# HB-Dis-EP-42BW.net
KiCad netlist of a schematic drawn in EAGLE
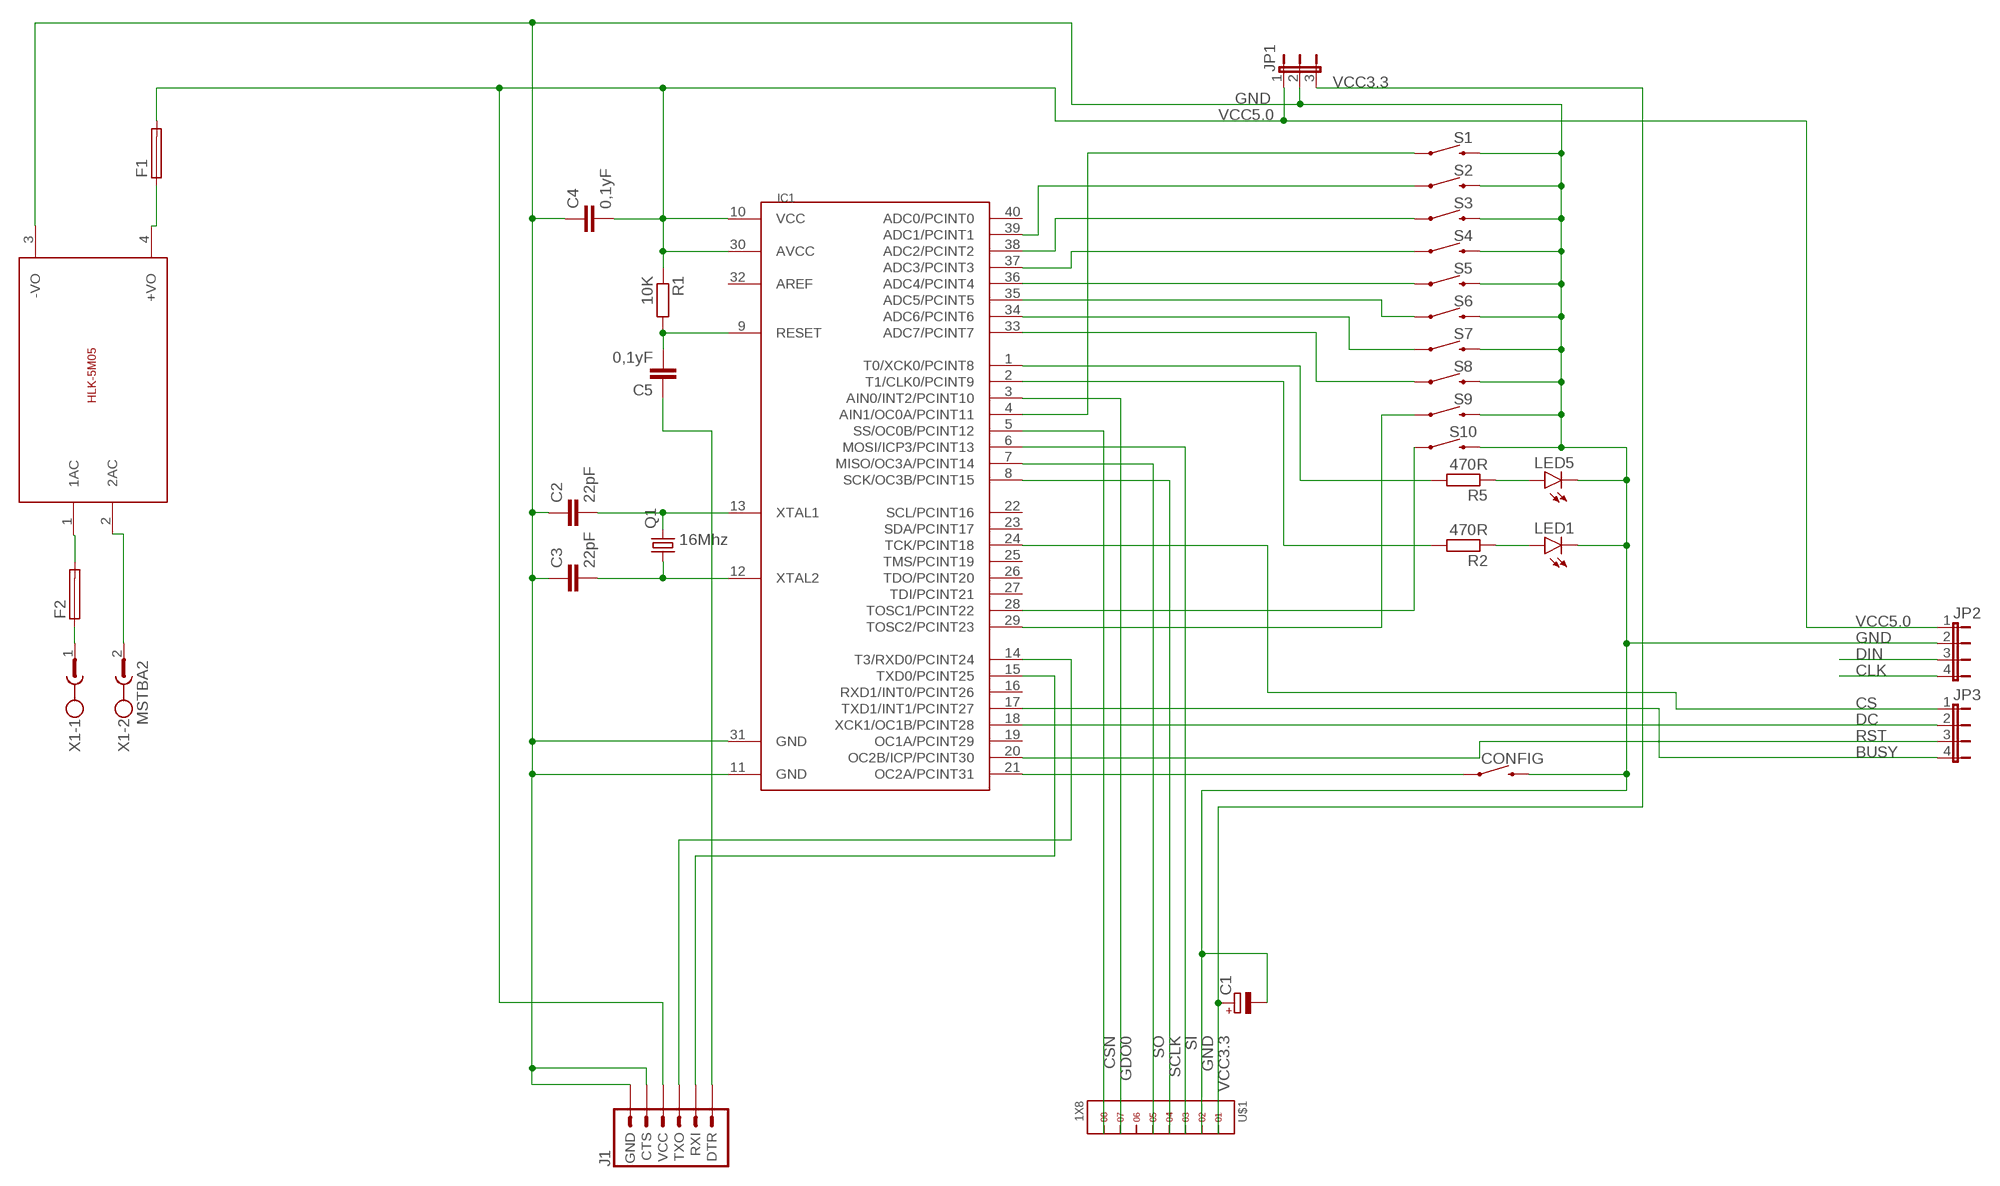
[diagram p0: schematic, sheet 1]

(export (version "E")
  (design (tool "Eeschema 10.0.6"))
  (components
    (comp (ref "C1")
      (value "CPOL-EUE2.5-5")
      (footprint "eagle-import:E2,5-5")
      (libsource (lib "eagle-import") (part "CPOL-EUE2.5-5"))
    )
    (comp (ref "C2")
      (value "22pF")
      (footprint "eagle-import:C025-024X044")
      (libsource (lib "eagle-import") (part "C-EU025-024X044"))
    )
    (comp (ref "C3")
      (value "22pF")
      (footprint "eagle-import:C025-024X044")
      (libsource (lib "eagle-import") (part "C-EU025-024X044"))
    )
    (comp (ref "C4")
      (value "0,1yF")
      (footprint "eagle-import:C025-024X044")
      (libsource (lib "eagle-import") (part "C-EU025-024X044"))
    )
    (comp (ref "C5")
      (value "0,1yF")
      (footprint "eagle-import:C025-024X044")
      (libsource (lib "eagle-import") (part "C-EU025-024X044"))
    )
    (comp (ref "CONFIG")
      (value "MOMENTARY-SWITCH-SPST-PTH-6.0MM-KIT")
      (footprint "eagle-import:TACTILE_SWITCH_PTH_6.0MM_KIT")
      (libsource (lib "eagle-import") (part "MOMENTARY-SWITCH-SPST-PTH-6.0MM-KIT"))
    )
    (comp (ref "F1")
      (value "SH22,5A")
      (footprint "eagle-import:SH22,5A")
      (fields (field (name "MPN") "0031.7701.11"))
      (libsource (lib "eagle-import") (part "SH22,5A"))
    )
    (comp (ref "F2")
      (value "SH22,5A")
      (footprint "eagle-import:SH22,5A")
      (fields (field (name "MPN") "0031.7701.11"))
      (libsource (lib "eagle-import") (part "SH22,5A"))
    )
    (comp (ref "IC1")
      (value "MEGA1284P")
      (footprint "eagle-import:DIL40")
      (libsource (lib "eagle-import") (part "MEGA1284P"))
    )
    (comp (ref "J1")
      (value "6_PIN_SERIAL_TARGETLONGPADS")
      (footprint "eagle-import:1X06_LONGPADS")
      (libsource (lib "eagle-import") (part "6_PIN_SERIAL_TARGETLONGPADS"))
    )
    (comp (ref "JP1")
      (value "JP2E")
      (footprint "eagle-import:JP2")
      (libsource (lib "eagle-import") (part "JP2E"))
    )
    (comp (ref "JP2")
      (value "JP4E")
      (footprint "eagle-import:JP4")
      (libsource (lib "eagle-import") (part "JP4E"))
    )
    (comp (ref "JP3")
      (value "JP4E")
      (footprint "eagle-import:JP4")
      (libsource (lib "eagle-import") (part "JP4E"))
    )
    (comp (ref "LED1")
      (value "LED3MM")
      (footprint "eagle-import:LED3MM")
      (libsource (lib "eagle-import") (part "LED3MM"))
    )
    (comp (ref "LED5")
      (value "LED3MM")
      (footprint "eagle-import:LED3MM")
      (libsource (lib "eagle-import") (part "LED3MM"))
    )
    (comp (ref "Q1")
      (value "16Mhz")
      (footprint "eagle-import:HC49U-V")
      (libsource (lib "eagle-import") (part "CRYSTALHC49U-V"))
    )
    (comp (ref "R1")
      (value "10K")
      (footprint "eagle-import:0309_10")
      (libsource (lib "eagle-import") (part "R-EU_0309/10"))
    )
    (comp (ref "R2")
      (value "470R")
      (footprint "eagle-import:0309_10")
      (libsource (lib "eagle-import") (part "R-EU_0309/10"))
    )
    (comp (ref "R5")
      (value "470R")
      (footprint "eagle-import:0309_10")
      (libsource (lib "eagle-import") (part "R-EU_0309/10"))
    )
    (comp (ref "S1")
      (value "MOMENTARY-SWITCH-SPST-PTH-6.0MM-KIT")
      (footprint "eagle-import:TACTILE_SWITCH_PTH_6.0MM_KIT")
      (libsource (lib "eagle-import") (part "MOMENTARY-SWITCH-SPST-PTH-6.0MM-KIT"))
    )
    (comp (ref "S2")
      (value "MOMENTARY-SWITCH-SPST-PTH-6.0MM-KIT")
      (footprint "eagle-import:TACTILE_SWITCH_PTH_6.0MM_KIT")
      (libsource (lib "eagle-import") (part "MOMENTARY-SWITCH-SPST-PTH-6.0MM-KIT"))
    )
    (comp (ref "S3")
      (value "MOMENTARY-SWITCH-SPST-PTH-6.0MM-KIT")
      (footprint "eagle-import:TACTILE_SWITCH_PTH_6.0MM_KIT")
      (libsource (lib "eagle-import") (part "MOMENTARY-SWITCH-SPST-PTH-6.0MM-KIT"))
    )
    (comp (ref "S4")
      (value "MOMENTARY-SWITCH-SPST-PTH-6.0MM-KIT")
      (footprint "eagle-import:TACTILE_SWITCH_PTH_6.0MM_KIT")
      (libsource (lib "eagle-import") (part "MOMENTARY-SWITCH-SPST-PTH-6.0MM-KIT"))
    )
    (comp (ref "S5")
      (value "MOMENTARY-SWITCH-SPST-PTH-6.0MM-KIT")
      (footprint "eagle-import:TACTILE_SWITCH_PTH_6.0MM_KIT")
      (libsource (lib "eagle-import") (part "MOMENTARY-SWITCH-SPST-PTH-6.0MM-KIT"))
    )
    (comp (ref "S6")
      (value "MOMENTARY-SWITCH-SPST-PTH-6.0MM-KIT")
      (footprint "eagle-import:TACTILE_SWITCH_PTH_6.0MM_KIT")
      (libsource (lib "eagle-import") (part "MOMENTARY-SWITCH-SPST-PTH-6.0MM-KIT"))
    )
    (comp (ref "S7")
      (value "MOMENTARY-SWITCH-SPST-PTH-6.0MM-KIT")
      (footprint "eagle-import:TACTILE_SWITCH_PTH_6.0MM_KIT")
      (libsource (lib "eagle-import") (part "MOMENTARY-SWITCH-SPST-PTH-6.0MM-KIT"))
    )
    (comp (ref "S8")
      (value "MOMENTARY-SWITCH-SPST-PTH-6.0MM-KIT")
      (footprint "eagle-import:TACTILE_SWITCH_PTH_6.0MM_KIT")
      (libsource (lib "eagle-import") (part "MOMENTARY-SWITCH-SPST-PTH-6.0MM-KIT"))
    )
    (comp (ref "S9")
      (value "MOMENTARY-SWITCH-SPST-PTH-6.0MM-KIT")
      (footprint "eagle-import:TACTILE_SWITCH_PTH_6.0MM_KIT")
      (libsource (lib "eagle-import") (part "MOMENTARY-SWITCH-SPST-PTH-6.0MM-KIT"))
    )
    (comp (ref "S10")
      (value "MOMENTARY-SWITCH-SPST-PTH-6.0MM-KIT")
      (footprint "eagle-import:TACTILE_SWITCH_PTH_6.0MM_KIT")
      (libsource (lib "eagle-import") (part "MOMENTARY-SWITCH-SPST-PTH-6.0MM-KIT"))
    )
    (comp (ref "U$1")
      (value "1X8")
      (footprint "eagle-import:1X8")
      (libsource (lib "eagle-import") (part "1X8"))
    )
    (comp (ref "U$3")
      (value "5VDC/5W")
      (footprint "eagle-import:HLK-5M05")
      (libsource (lib "eagle-import") (part "HLK-5M05"))
    )
    (comp (ref "X1")
      (value "MSTBA2")
      (footprint "eagle-import:MSTBA2")
      (fields (field (name "MF") "FARNELL") (field (name "MPN") "1757242"))
      (libsource (lib "eagle-import") (part "MSTBA2"))
    )
  )
  (nets
    (net (code "1") (name "/BUSY") (class "Default")
      (node (ref "IC1") (pin "17") (pinfunction "TXD1/INT1/PCINT27_17") (pintype "bidirectional"))
      (node (ref "JP3") (pin "4") (pinfunction "4_4") (pintype "passive"))
    )
    (net (code "2") (name "/CLK") (class "Default")
      (node (ref "JP2") (pin "4") (pinfunction "4_4") (pintype "passive"))
    )
    (net (code "3") (name "/CS") (class "Default")
      (node (ref "IC1") (pin "24") (pinfunction "TCK/PCINT18_24") (pintype "bidirectional"))
      (node (ref "JP3") (pin "1") (pinfunction "1_1") (pintype "passive"))
    )
    (net (code "4") (name "/CSN") (class "Default")
      (node (ref "IC1") (pin "5") (pinfunction "SS/OC0B/PCINT12_5") (pintype "bidirectional"))
      (node (ref "U$1") (pin "8") (pinfunction "8_8") (pintype "bidirectional"))
    )
    (net (code "5") (name "/DC") (class "Default")
      (node (ref "IC1") (pin "18") (pinfunction "XCK1/OC1B/PCINT28_18") (pintype "bidirectional"))
      (node (ref "JP3") (pin "2") (pinfunction "2_2") (pintype "passive"))
    )
    (net (code "6") (name "/DIN") (class "Default")
      (node (ref "JP2") (pin "3") (pinfunction "3_3") (pintype "passive"))
    )
    (net (code "7") (name "/GDO0") (class "Default")
      (node (ref "IC1") (pin "3") (pinfunction "AIN0/INT2/PCINT10_3") (pintype "bidirectional"))
      (node (ref "U$1") (pin "7") (pinfunction "7_7") (pintype "bidirectional"))
    )
    (net (code "8") (name "/GND") (class "Default")
      (node (ref "C1") (pin "-") (pinfunction "-_-") (pintype "passive"))
      (node (ref "C2") (pin "1") (pinfunction "1_1") (pintype "passive"))
      (node (ref "C3") (pin "1") (pinfunction "1_1") (pintype "passive"))
      (node (ref "C4") (pin "1") (pinfunction "1_1") (pintype "passive"))
      (node (ref "CONFIG") (pin "3") (pinfunction "2_3") (pintype "passive"))
      (node (ref "IC1") (pin "11") (pinfunction "GND_11") (pintype "bidirectional"))
      (node (ref "IC1") (pin "31") (pinfunction "GND_31") (pintype "bidirectional"))
      (node (ref "J1") (pin "5") (pinfunction "CTS_5") (pintype "passive"))
      (node (ref "J1") (pin "6") (pinfunction "GND_6") (pintype "passive"))
      (node (ref "JP1") (pin "2") (pinfunction "2_2") (pintype "passive"))
      (node (ref "JP2") (pin "2") (pinfunction "2_2") (pintype "passive"))
      (node (ref "LED1") (pin "K") (pinfunction "C_K") (pintype "passive"))
      (node (ref "LED5") (pin "K") (pinfunction "C_K") (pintype "passive"))
      (node (ref "S1") (pin "3") (pinfunction "2_3") (pintype "passive"))
      (node (ref "S10") (pin "3") (pinfunction "2_3") (pintype "passive"))
      (node (ref "S2") (pin "3") (pinfunction "2_3") (pintype "passive"))
      (node (ref "S3") (pin "3") (pinfunction "2_3") (pintype "passive"))
      (node (ref "S4") (pin "3") (pinfunction "2_3") (pintype "passive"))
      (node (ref "S5") (pin "3") (pinfunction "2_3") (pintype "passive"))
      (node (ref "S6") (pin "3") (pinfunction "2_3") (pintype "passive"))
      (node (ref "S7") (pin "3") (pinfunction "2_3") (pintype "passive"))
      (node (ref "S8") (pin "3") (pinfunction "2_3") (pintype "passive"))
      (node (ref "S9") (pin "3") (pinfunction "2_3") (pintype "passive"))
      (node (ref "U$1") (pin "2") (pinfunction "2_2") (pintype "bidirectional"))
      (node (ref "U$3") (pin "3") (pinfunction "-VO_3") (pintype "bidirectional"))
    )
    (net (code "9") (name "/RST") (class "Default")
      (node (ref "IC1") (pin "20") (pinfunction "OC2B/ICP/PCINT30_20") (pintype "bidirectional"))
      (node (ref "JP3") (pin "3") (pinfunction "3_3") (pintype "passive"))
    )
    (net (code "10") (name "/SCLK") (class "Default")
      (node (ref "IC1") (pin "8") (pinfunction "SCK/OC3B/PCINT15_8") (pintype "bidirectional"))
      (node (ref "U$1") (pin "4") (pinfunction "4_4") (pintype "bidirectional"))
    )
    (net (code "11") (name "/SI") (class "Default")
      (node (ref "IC1") (pin "6") (pinfunction "MOSI/ICP3/PCINT13_6") (pintype "bidirectional"))
      (node (ref "U$1") (pin "3") (pinfunction "3_3") (pintype "bidirectional"))
    )
    (net (code "12") (name "/SO") (class "Default")
      (node (ref "IC1") (pin "7") (pinfunction "MISO/OC3A/PCINT14_7") (pintype "bidirectional"))
      (node (ref "U$1") (pin "5") (pinfunction "5_5") (pintype "bidirectional"))
    )
    (net (code "13") (name "/VCC3.3") (class "Default")
      (node (ref "C1") (pin "+") (pinfunction "+_+") (pintype "passive"))
      (node (ref "JP1") (pin "3") (pinfunction "3_3") (pintype "passive"))
      (node (ref "U$1") (pin "1") (pinfunction "1_1") (pintype "bidirectional"))
    )
    (net (code "14") (name "/VCC5.0") (class "Default")
      (node (ref "C4") (pin "2") (pinfunction "2_2") (pintype "passive"))
      (node (ref "F1") (pin "2") (pinfunction "2_2") (pintype "passive"))
      (node (ref "IC1") (pin "10") (pinfunction "VCC_10") (pintype "bidirectional"))
      (node (ref "IC1") (pin "30") (pinfunction "AVCC_30") (pintype "bidirectional"))
      (node (ref "J1") (pin "4") (pinfunction "VCC_4") (pintype "passive"))
      (node (ref "JP1") (pin "1") (pinfunction "1_1") (pintype "passive"))
      (node (ref "JP2") (pin "1") (pinfunction "1_1") (pintype "passive"))
      (node (ref "R1") (pin "1") (pinfunction "1_1") (pintype "passive"))
    )
    (net (code "15") (name "Net-(F2-Pad1)") (class "Default")
      (node (ref "F2") (pin "1") (pinfunction "1_1") (pintype "passive"))
      (node (ref "X1") (pin "1") (pinfunction "1_1") (pintype "passive"))
    )
    (net (code "16") (name "Net-(IC1-ADC1{slash}PCINT1)") (class "Default")
      (node (ref "IC1") (pin "39") (pinfunction "ADC1/PCINT1_39") (pintype "bidirectional"))
      (node (ref "S2") (pin "1") (pinfunction "1_1") (pintype "passive"))
    )
    (net (code "17") (name "Net-(IC1-ADC2{slash}PCINT2)") (class "Default")
      (node (ref "IC1") (pin "38") (pinfunction "ADC2/PCINT2_38") (pintype "bidirectional"))
      (node (ref "S3") (pin "1") (pinfunction "1_1") (pintype "passive"))
    )
    (net (code "18") (name "Net-(IC1-ADC3{slash}PCINT3)") (class "Default")
      (node (ref "IC1") (pin "37") (pinfunction "ADC3/PCINT3_37") (pintype "bidirectional"))
      (node (ref "S4") (pin "1") (pinfunction "1_1") (pintype "passive"))
    )
    (net (code "19") (name "Net-(IC1-ADC4{slash}PCINT4)") (class "Default")
      (node (ref "IC1") (pin "36") (pinfunction "ADC4/PCINT4_36") (pintype "bidirectional"))
      (node (ref "S5") (pin "1") (pinfunction "1_1") (pintype "passive"))
    )
    (net (code "20") (name "Net-(IC1-ADC5{slash}PCINT5)") (class "Default")
      (node (ref "IC1") (pin "35") (pinfunction "ADC5/PCINT5_35") (pintype "bidirectional"))
      (node (ref "S6") (pin "1") (pinfunction "1_1") (pintype "passive"))
    )
    (net (code "21") (name "Net-(IC1-ADC6{slash}PCINT6)") (class "Default")
      (node (ref "IC1") (pin "34") (pinfunction "ADC6/PCINT6_34") (pintype "bidirectional"))
      (node (ref "S7") (pin "1") (pinfunction "1_1") (pintype "passive"))
    )
    (net (code "22") (name "Net-(IC1-ADC7{slash}PCINT7)") (class "Default")
      (node (ref "IC1") (pin "33") (pinfunction "ADC7/PCINT7_33") (pintype "bidirectional"))
      (node (ref "S8") (pin "1") (pinfunction "1_1") (pintype "passive"))
    )
    (net (code "23") (name "Net-(IC1-AIN1{slash}OC0A{slash}PCINT11)") (class "Default")
      (node (ref "IC1") (pin "4") (pinfunction "AIN1/OC0A/PCINT11_4") (pintype "bidirectional"))
      (node (ref "S1") (pin "1") (pinfunction "1_1") (pintype "passive"))
    )
    (net (code "24") (name "Net-(IC1-OC2A{slash}PCINT31)") (class "Default")
      (node (ref "CONFIG") (pin "1") (pinfunction "1_1") (pintype "passive"))
      (node (ref "IC1") (pin "21") (pinfunction "OC2A/PCINT31_21") (pintype "bidirectional"))
    )
    (net (code "25") (name "Net-(IC1-RESET)") (class "Default")
      (node (ref "C5") (pin "2") (pinfunction "2_2") (pintype "passive"))
      (node (ref "IC1") (pin "9") (pinfunction "RESET_9") (pintype "bidirectional"))
      (node (ref "R1") (pin "2") (pinfunction "2_2") (pintype "passive"))
    )
    (net (code "26") (name "Net-(IC1-T0{slash}XCK0{slash}PCINT8)") (class "Default")
      (node (ref "IC1") (pin "1") (pinfunction "T0/XCK0/PCINT8_1") (pintype "bidirectional"))
      (node (ref "R5") (pin "2") (pinfunction "2_2") (pintype "passive"))
    )
    (net (code "27") (name "Net-(IC1-T1{slash}CLK0{slash}PCINT9)") (class "Default")
      (node (ref "IC1") (pin "2") (pinfunction "T1/CLK0/PCINT9_2") (pintype "bidirectional"))
      (node (ref "R2") (pin "2") (pinfunction "2_2") (pintype "passive"))
    )
    (net (code "28") (name "Net-(IC1-T3{slash}RXD0{slash}PCINT24)") (class "Default")
      (node (ref "IC1") (pin "14") (pinfunction "T3/RXD0/PCINT24_14") (pintype "bidirectional"))
      (node (ref "J1") (pin "3") (pinfunction "TXO_3") (pintype "passive"))
    )
    (net (code "29") (name "Net-(IC1-TOSC1{slash}PCINT22)") (class "Default")
      (node (ref "IC1") (pin "28") (pinfunction "TOSC1/PCINT22_28") (pintype "bidirectional"))
      (node (ref "S10") (pin "1") (pinfunction "1_1") (pintype "passive"))
    )
    (net (code "30") (name "Net-(IC1-TOSC2{slash}PCINT23)") (class "Default")
      (node (ref "IC1") (pin "29") (pinfunction "TOSC2/PCINT23_29") (pintype "bidirectional"))
      (node (ref "S9") (pin "1") (pinfunction "1_1") (pintype "passive"))
    )
    (net (code "31") (name "Net-(IC1-TXD0{slash}PCINT25)") (class "Default")
      (node (ref "IC1") (pin "15") (pinfunction "TXD0/PCINT25_15") (pintype "bidirectional"))
      (node (ref "J1") (pin "2") (pinfunction "RXI_2") (pintype "passive"))
    )
    (net (code "32") (name "Net-(IC1-XTAL1)") (class "Default")
      (node (ref "C2") (pin "2") (pinfunction "2_2") (pintype "passive"))
      (node (ref "IC1") (pin "13") (pinfunction "XTAL1_13") (pintype "bidirectional"))
      (node (ref "Q1") (pin "2") (pinfunction "2_2") (pintype "passive"))
    )
    (net (code "33") (name "Net-(IC1-XTAL2)") (class "Default")
      (node (ref "C3") (pin "2") (pinfunction "2_2") (pintype "passive"))
      (node (ref "IC1") (pin "12") (pinfunction "XTAL2_12") (pintype "bidirectional"))
      (node (ref "Q1") (pin "1") (pinfunction "1_1") (pintype "passive"))
    )
    (net (code "34") (name "Net-(J1-DTR)") (class "Default")
      (node (ref "C5") (pin "1") (pinfunction "1_1") (pintype "passive"))
      (node (ref "J1") (pin "1") (pinfunction "DTR_1") (pintype "passive"))
    )
    (net (code "35") (name "Net-(LED1-PadA)") (class "Default")
      (node (ref "LED1") (pin "A") (pinfunction "A_A") (pintype "passive"))
      (node (ref "R2") (pin "1") (pinfunction "1_1") (pintype "passive"))
    )
    (net (code "36") (name "Net-(LED5-PadA)") (class "Default")
      (node (ref "LED5") (pin "A") (pinfunction "A_A") (pintype "passive"))
      (node (ref "R5") (pin "1") (pinfunction "1_1") (pintype "passive"))
    )
    (net (code "37") (name "Net-(U$3-+VO)") (class "Default")
      (node (ref "F1") (pin "1") (pinfunction "1_1") (pintype "passive"))
      (node (ref "U$3") (pin "4") (pinfunction "+VO_4") (pintype "bidirectional"))
    )
    (net (code "38") (name "Net-(U$3-1AC)") (class "Default")
      (node (ref "F2") (pin "2") (pinfunction "2_2") (pintype "passive"))
      (node (ref "U$3") (pin "1") (pinfunction "1AC_1") (pintype "bidirectional"))
    )
    (net (code "39") (name "Net-(U$3-2AC)") (class "Default")
      (node (ref "U$3") (pin "2") (pinfunction "2AC_2") (pintype "bidirectional"))
      (node (ref "X1") (pin "2") (pinfunction "1_2") (pintype "passive"))
    )
    (net (code "40") (name "unconnected-(IC1-ADC0{slash}PCINT0-Pad40)") (class "Default")
      (node (ref "IC1") (pin "40") (pinfunction "ADC0/PCINT0_40") (pintype "bidirectional"))
    )
    (net (code "41") (name "unconnected-(IC1-AREF-Pad32)") (class "Default")
      (node (ref "IC1") (pin "32") (pinfunction "AREF_32") (pintype "bidirectional"))
    )
    (net (code "42") (name "unconnected-(IC1-OC1A{slash}PCINT29-Pad19)") (class "Default")
      (node (ref "IC1") (pin "19") (pinfunction "OC1A/PCINT29_19") (pintype "bidirectional"))
    )
    (net (code "43") (name "unconnected-(IC1-RXD1{slash}INT0{slash}PCINT26-Pad16)") (class "Default")
      (node (ref "IC1") (pin "16") (pinfunction "RXD1/INT0/PCINT26_16") (pintype "bidirectional"))
    )
    (net (code "44") (name "unconnected-(IC1-SCL{slash}PCINT16-Pad22)") (class "Default")
      (node (ref "IC1") (pin "22") (pinfunction "SCL/PCINT16_22") (pintype "bidirectional"))
    )
    (net (code "45") (name "unconnected-(IC1-SDA{slash}PCINT17-Pad23)") (class "Default")
      (node (ref "IC1") (pin "23") (pinfunction "SDA/PCINT17_23") (pintype "bidirectional"))
    )
    (net (code "46") (name "unconnected-(IC1-TDI{slash}PCINT21-Pad27)") (class "Default")
      (node (ref "IC1") (pin "27") (pinfunction "TDI/PCINT21_27") (pintype "bidirectional"))
    )
    (net (code "47") (name "unconnected-(IC1-TDO{slash}PCINT20-Pad26)") (class "Default")
      (node (ref "IC1") (pin "26") (pinfunction "TDO/PCINT20_26") (pintype "bidirectional"))
    )
    (net (code "48") (name "unconnected-(IC1-TMS{slash}PCINT19-Pad25)") (class "Default")
      (node (ref "IC1") (pin "25") (pinfunction "TMS/PCINT19_25") (pintype "bidirectional"))
    )
    (net (code "49") (name "unconnected-(U$1-Pad6)") (class "Default")
      (node (ref "U$1") (pin "6") (pinfunction "6_6") (pintype "bidirectional"))
    )
  )
)
